# Adafruit_LED_Arcade_Button_1x4.net
KiCad netlist of a schematic drawn in EAGLE
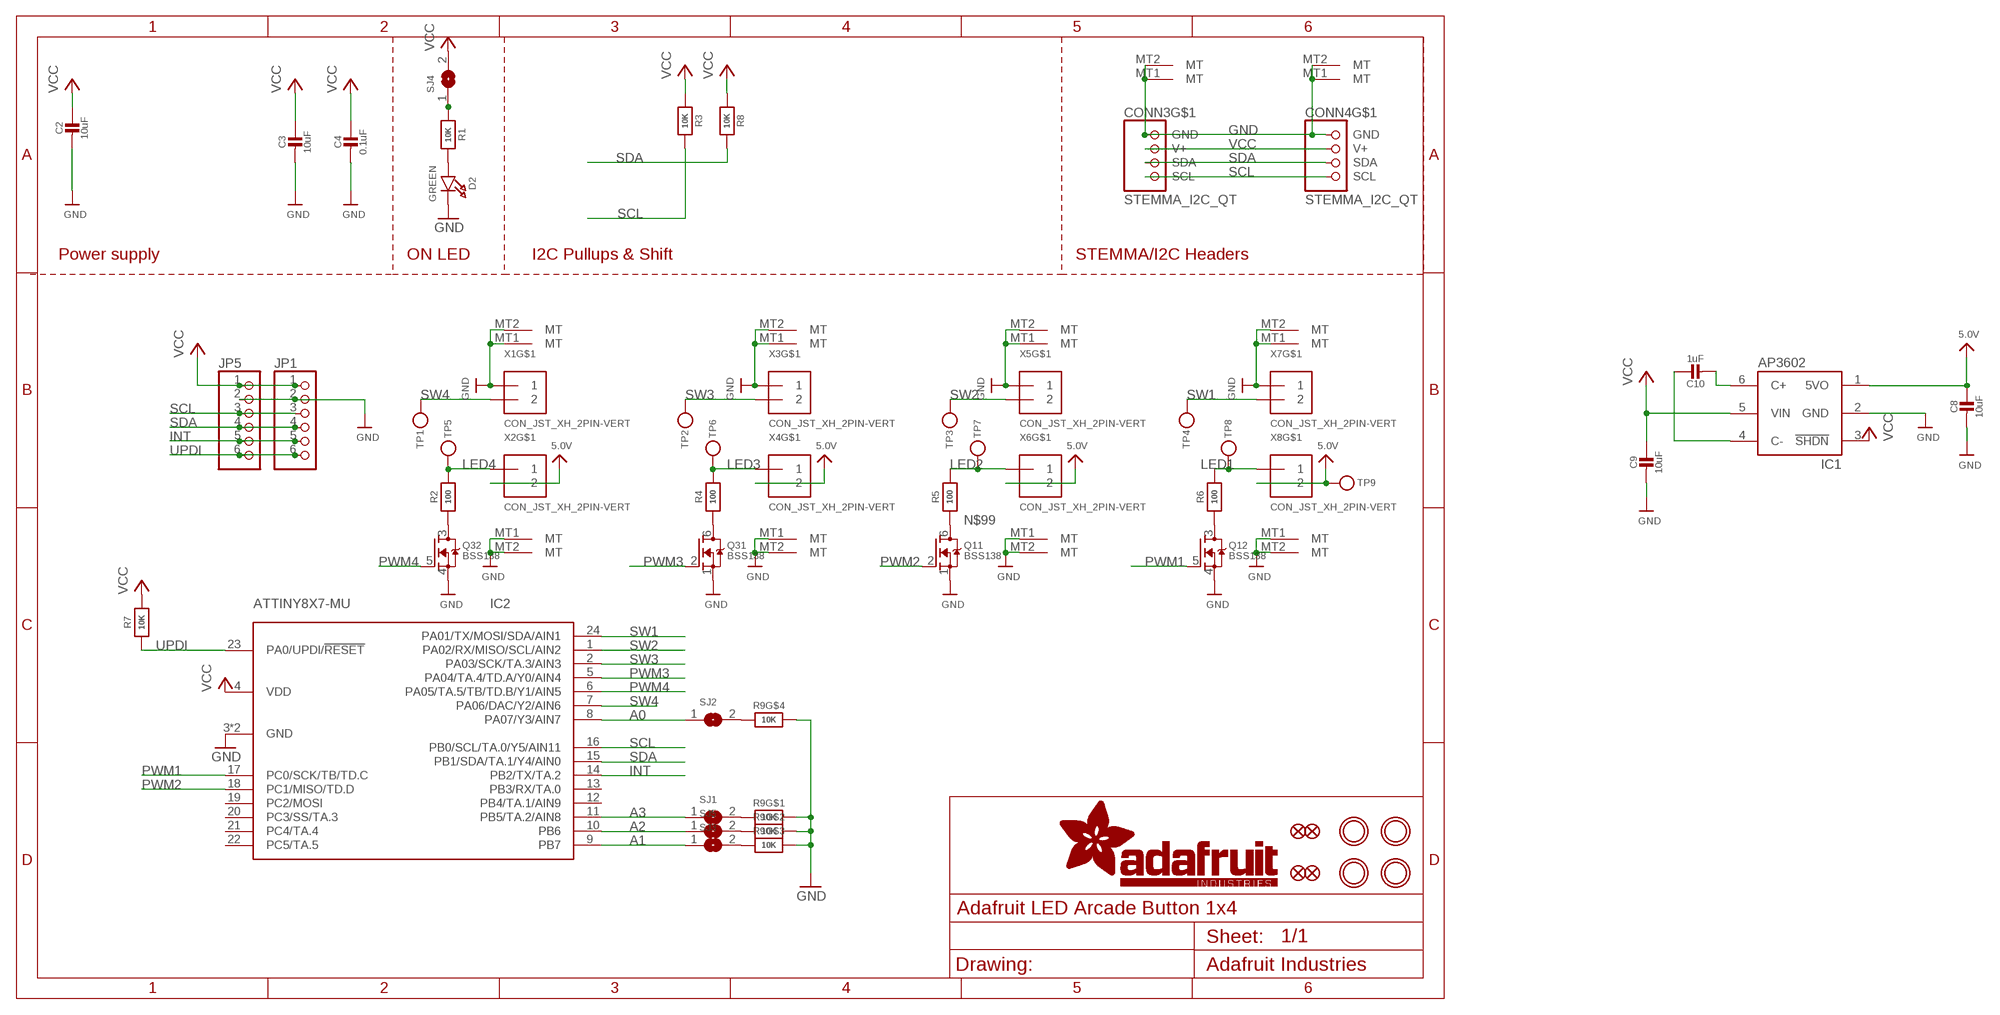
[diagram p0: schematic, sheet 1]

(export (version "E")
  (design (tool "Eeschema 10.0.6"))
  (components
    (comp (ref "C2")
      (value "10uF")
      (footprint "eagle-import:0805-NO")
      (libsource (lib "eagle-import") (part "CAP_CERAMIC0805-NOOUTLINE"))
    )
    (comp (ref "C3")
      (value "10uF")
      (footprint "eagle-import:0805-NO")
      (libsource (lib "eagle-import") (part "CAP_CERAMIC0805-NOOUTLINE"))
    )
    (comp (ref "C4")
      (value "0.1uF")
      (footprint "eagle-import:0603-NO")
      (libsource (lib "eagle-import") (part "CAP_CERAMIC0603_NO"))
    )
    (comp (ref "C8")
      (value "10uF")
      (footprint "eagle-import:0805-NO")
      (libsource (lib "eagle-import") (part "CAP_CERAMIC0805-NOOUTLINE"))
    )
    (comp (ref "C9")
      (value "10uF")
      (footprint "eagle-import:0805-NO")
      (libsource (lib "eagle-import") (part "CAP_CERAMIC0805-NOOUTLINE"))
    )
    (comp (ref "C10")
      (value "1uF")
      (footprint "eagle-import:0805-NO")
      (libsource (lib "eagle-import") (part "CAP_CERAMIC0805-NOOUTLINE"))
    )
    (comp (ref "CONN3")
      (value "STEMMA_I2C_QT")
      (footprint "eagle-import:JST_SH4")
      (libsource (lib "eagle-import") (part "STEMMA_I2C_QT"))
    )
    (comp (ref "CONN4")
      (value "STEMMA_I2C_QT")
      (footprint "eagle-import:JST_SH4")
      (libsource (lib "eagle-import") (part "STEMMA_I2C_QT"))
    )
    (comp (ref "D2")
      (value "GREEN")
      (footprint "eagle-import:CHIPLED_0603_NOOUTLINE")
      (libsource (lib "eagle-import") (part "LED0603_NOOUTLINE"))
    )
    (comp (ref "FID1")
      (value "FIDUCIAL_1MM")
      (footprint "eagle-import:FIDUCIAL_1MM")
      (libsource (lib "eagle-import") (part "FIDUCIAL_1MM"))
    )
    (comp (ref "FID2")
      (value "FIDUCIAL_1MM")
      (footprint "eagle-import:FIDUCIAL_1MM")
      (libsource (lib "eagle-import") (part "FIDUCIAL_1MM"))
    )
    (comp (ref "FID3")
      (value "FIDUCIAL_1MM")
      (footprint "eagle-import:FIDUCIAL_1MM")
      (libsource (lib "eagle-import") (part "FIDUCIAL_1MM"))
    )
    (comp (ref "FID4")
      (value "FIDUCIAL_1MM")
      (footprint "eagle-import:FIDUCIAL_1MM")
      (libsource (lib "eagle-import") (part "FIDUCIAL_1MM"))
    )
    (comp (ref "IC1")
      (value "AP3602")
      (footprint "eagle-import:SOT23-6")
      (libsource (lib "eagle-import") (part "AP3602"))
    )
    (comp (ref "IC2")
      (value "ATTINY8X7-MU")
      (footprint "eagle-import:QFN24_4MM")
      (libsource (lib "eagle-import") (part "ATTINY8X7-MU"))
    )
    (comp (ref "JP1")
      (value "HEADER-1X670MIL")
      (footprint "eagle-import:1X06_ROUND_70")
      (libsource (lib "eagle-import") (part "HEADER-1X670MIL"))
    )
    (comp (ref "JP5")
      (value "HEADER-1X670MIL")
      (footprint "eagle-import:1X06_ROUND_70")
      (libsource (lib "eagle-import") (part "HEADER-1X670MIL"))
    )
    (comp (ref "Q1")
      (value "BSS138")
      (footprint "eagle-import:SOT363")
      (libsource (lib "eagle-import") (part "MOSFET-N_DUAL"))
    )
    (comp (ref "Q3")
      (value "BSS138")
      (footprint "eagle-import:SOT363")
      (libsource (lib "eagle-import") (part "MOSFET-N_DUAL"))
    )
    (comp (ref "R1")
      (value "10K")
      (footprint "eagle-import:0603-NO")
      (libsource (lib "eagle-import") (part "RESISTOR_0603_NOOUT"))
    )
    (comp (ref "R2")
      (value "100")
      (footprint "eagle-import:0603-NO")
      (libsource (lib "eagle-import") (part "RESISTOR_0603_NOOUT"))
    )
    (comp (ref "R3")
      (value "10K")
      (footprint "eagle-import:0603-NO")
      (libsource (lib "eagle-import") (part "RESISTOR_0603_NOOUT"))
    )
    (comp (ref "R4")
      (value "100")
      (footprint "eagle-import:0603-NO")
      (libsource (lib "eagle-import") (part "RESISTOR_0603_NOOUT"))
    )
    (comp (ref "R5")
      (value "100")
      (footprint "eagle-import:0603-NO")
      (libsource (lib "eagle-import") (part "RESISTOR_0603_NOOUT"))
    )
    (comp (ref "R6")
      (value "100")
      (footprint "eagle-import:0603-NO")
      (libsource (lib "eagle-import") (part "RESISTOR_0603_NOOUT"))
    )
    (comp (ref "R7")
      (value "10K")
      (footprint "eagle-import:0603-NO")
      (libsource (lib "eagle-import") (part "RESISTOR_0603_NOOUT"))
    )
    (comp (ref "R8")
      (value "10K")
      (footprint "eagle-import:0603-NO")
      (libsource (lib "eagle-import") (part "RESISTOR_0603_NOOUT"))
    )
    (comp (ref "R9")
      (value "10K")
      (footprint "eagle-import:RESPACK_4X0603")
      (libsource (lib "eagle-import") (part "RESISTOR_4PACK"))
    )
    (comp (ref "SJ1")
      (value "SOLDERJUMPERCLOSED")
      (footprint "eagle-import:SOLDERJUMPER_CLOSEDWIRE")
      (libsource (lib "eagle-import") (part "SOLDERJUMPERCLOSED"))
    )
    (comp (ref "SJ2")
      (value "SOLDERJUMPERCLOSED")
      (footprint "eagle-import:SOLDERJUMPER_CLOSEDWIRE")
      (libsource (lib "eagle-import") (part "SOLDERJUMPERCLOSED"))
    )
    (comp (ref "SJ3")
      (value "SOLDERJUMPERCLOSED")
      (footprint "eagle-import:SOLDERJUMPER_CLOSEDWIRE")
      (libsource (lib "eagle-import") (part "SOLDERJUMPERCLOSED"))
    )
    (comp (ref "SJ4")
      (value "SOLDERJUMPERCLOSED")
      (footprint "eagle-import:SOLDERJUMPER_CLOSEDWIRE")
      (libsource (lib "eagle-import") (part "SOLDERJUMPERCLOSED"))
    )
    (comp (ref "SJ5")
      (value "SOLDERJUMPERCLOSED")
      (footprint "eagle-import:SOLDERJUMPER_CLOSEDWIRE")
      (libsource (lib "eagle-import") (part "SOLDERJUMPERCLOSED"))
    )
    (comp (ref "TP1")
      (value "TESTPOINTROUND1.5MM")
      (footprint "eagle-import:TESTPOINT_ROUND_1.5MM")
      (libsource (lib "eagle-import") (part "TESTPOINTROUND1.5MM"))
    )
    (comp (ref "TP2")
      (value "TESTPOINTROUND1.5MM")
      (footprint "eagle-import:TESTPOINT_ROUND_1.5MM")
      (libsource (lib "eagle-import") (part "TESTPOINTROUND1.5MM"))
    )
    (comp (ref "TP3")
      (value "TESTPOINTROUND1.5MM")
      (footprint "eagle-import:TESTPOINT_ROUND_1.5MM")
      (libsource (lib "eagle-import") (part "TESTPOINTROUND1.5MM"))
    )
    (comp (ref "TP4")
      (value "TESTPOINTROUND1.5MM")
      (footprint "eagle-import:TESTPOINT_ROUND_1.5MM")
      (libsource (lib "eagle-import") (part "TESTPOINTROUND1.5MM"))
    )
    (comp (ref "TP5")
      (value "TESTPOINTROUND1.5MM")
      (footprint "eagle-import:TESTPOINT_ROUND_1.5MM")
      (libsource (lib "eagle-import") (part "TESTPOINTROUND1.5MM"))
    )
    (comp (ref "TP6")
      (value "TESTPOINTROUND1.5MM")
      (footprint "eagle-import:TESTPOINT_ROUND_1.5MM")
      (libsource (lib "eagle-import") (part "TESTPOINTROUND1.5MM"))
    )
    (comp (ref "TP7")
      (value "TESTPOINTROUND1.5MM")
      (footprint "eagle-import:TESTPOINT_ROUND_1.5MM")
      (libsource (lib "eagle-import") (part "TESTPOINTROUND1.5MM"))
    )
    (comp (ref "TP8")
      (value "TESTPOINTROUND1.5MM")
      (footprint "eagle-import:TESTPOINT_ROUND_1.5MM")
      (libsource (lib "eagle-import") (part "TESTPOINTROUND1.5MM"))
    )
    (comp (ref "TP9")
      (value "TESTPOINTROUND1.5MM")
      (footprint "eagle-import:TESTPOINT_ROUND_1.5MM")
      (libsource (lib "eagle-import") (part "TESTPOINTROUND1.5MM"))
    )
    (comp (ref "U$3")
      (value "MOUNTINGHOLE2.5")
      (footprint "eagle-import:MOUNTINGHOLE_2.5_PLATED")
      (libsource (lib "eagle-import") (part "MOUNTINGHOLE2.5"))
    )
    (comp (ref "U$17")
      (value "MOUNTINGHOLE2.5")
      (footprint "eagle-import:MOUNTINGHOLE_2.5_PLATED")
      (libsource (lib "eagle-import") (part "MOUNTINGHOLE2.5"))
    )
    (comp (ref "U$19")
      (value "MOUNTINGHOLE2.5")
      (footprint "eagle-import:MOUNTINGHOLE_2.5_PLATED")
      (libsource (lib "eagle-import") (part "MOUNTINGHOLE2.5"))
    )
    (comp (ref "U$21")
      (value "MOUNTINGHOLE2.5")
      (footprint "eagle-import:MOUNTINGHOLE_2.5_PLATED")
      (libsource (lib "eagle-import") (part "MOUNTINGHOLE2.5"))
    )
    (comp (ref "X1")
      (value "CON_JST_XH_2PIN-VERT")
      (footprint "eagle-import:JST-XH-2-SV")
      (libsource (lib "eagle-import") (part "CON_JST_XH_2PIN-VERT"))
    )
    (comp (ref "X2")
      (value "CON_JST_XH_2PIN-VERT")
      (footprint "eagle-import:JST-XH-2-SV")
      (libsource (lib "eagle-import") (part "CON_JST_XH_2PIN-VERT"))
    )
    (comp (ref "X3")
      (value "CON_JST_XH_2PIN-VERT")
      (footprint "eagle-import:JST-XH-2-SV")
      (libsource (lib "eagle-import") (part "CON_JST_XH_2PIN-VERT"))
    )
    (comp (ref "X4")
      (value "CON_JST_XH_2PIN-VERT")
      (footprint "eagle-import:JST-XH-2-SV")
      (libsource (lib "eagle-import") (part "CON_JST_XH_2PIN-VERT"))
    )
    (comp (ref "X5")
      (value "CON_JST_XH_2PIN-VERT")
      (footprint "eagle-import:JST-XH-2-SV")
      (libsource (lib "eagle-import") (part "CON_JST_XH_2PIN-VERT"))
    )
    (comp (ref "X6")
      (value "CON_JST_XH_2PIN-VERT")
      (footprint "eagle-import:JST-XH-2-SV")
      (libsource (lib "eagle-import") (part "CON_JST_XH_2PIN-VERT"))
    )
    (comp (ref "X7")
      (value "CON_JST_XH_2PIN-VERT")
      (footprint "eagle-import:JST-XH-2-SV")
      (libsource (lib "eagle-import") (part "CON_JST_XH_2PIN-VERT"))
    )
    (comp (ref "X8")
      (value "CON_JST_XH_2PIN-VERT")
      (footprint "eagle-import:JST-XH-2-SV")
      (libsource (lib "eagle-import") (part "CON_JST_XH_2PIN-VERT"))
    )
  )
  (nets
    (net (code "1") (name "/A0") (class "Default")
      (node (ref "IC2") (pin "8") (pinfunction "PA07/Y3/AIN7_8") (pintype "bidirectional"))
      (node (ref "SJ2") (pin "1") (pinfunction "1_1") (pintype "passive"))
    )
    (net (code "2") (name "/A1") (class "Default")
      (node (ref "IC2") (pin "9") (pinfunction "PB7_9") (pintype "bidirectional"))
      (node (ref "SJ3") (pin "1") (pinfunction "1_1") (pintype "passive"))
    )
    (net (code "3") (name "/A2") (class "Default")
      (node (ref "IC2") (pin "10") (pinfunction "PB6_10") (pintype "bidirectional"))
      (node (ref "SJ5") (pin "1") (pinfunction "1_1") (pintype "passive"))
    )
    (net (code "4") (name "/A3") (class "Default")
      (node (ref "IC2") (pin "11") (pinfunction "PB5/TA.2/AIN8_11") (pintype "bidirectional"))
      (node (ref "SJ1") (pin "1") (pinfunction "1_1") (pintype "passive"))
    )
    (net (code "5") (name "/INT") (class "Default")
      (node (ref "IC2") (pin "14") (pinfunction "PB2/TX/TA.2_14") (pintype "bidirectional"))
      (node (ref "JP1") (pin "5") (pinfunction "5_5") (pintype "passive"))
      (node (ref "JP5") (pin "5") (pinfunction "5_5") (pintype "passive"))
    )
    (net (code "6") (name "/LED1") (class "Default")
      (node (ref "R6") (pin "2") (pinfunction "2_2") (pintype "passive"))
      (node (ref "TP8") (pin "P$1") (pinfunction "P$1_P$1") (pintype "bidirectional"))
      (node (ref "X8") (pin "1") (pinfunction "1_1") (pintype "passive"))
    )
    (net (code "7") (name "/LED2") (class "Default")
      (node (ref "R5") (pin "2") (pinfunction "2_2") (pintype "passive"))
      (node (ref "TP7") (pin "P$1") (pinfunction "P$1_P$1") (pintype "bidirectional"))
      (node (ref "X6") (pin "1") (pinfunction "1_1") (pintype "passive"))
    )
    (net (code "8") (name "/LED3") (class "Default")
      (node (ref "R4") (pin "2") (pinfunction "2_2") (pintype "passive"))
      (node (ref "TP6") (pin "P$1") (pinfunction "P$1_P$1") (pintype "bidirectional"))
      (node (ref "X4") (pin "1") (pinfunction "1_1") (pintype "passive"))
    )
    (net (code "9") (name "/LED4") (class "Default")
      (node (ref "R2") (pin "2") (pinfunction "2_2") (pintype "passive"))
      (node (ref "TP5") (pin "P$1") (pinfunction "P$1_P$1") (pintype "bidirectional"))
      (node (ref "X2") (pin "1") (pinfunction "1_1") (pintype "passive"))
    )
    (net (code "11") (name "/PWM1") (class "Default")
      (node (ref "IC2") (pin "17") (pinfunction "PC0/SCK/TB/TD.C_17") (pintype "bidirectional"))
      (node (ref "Q1") (pin "5") (pinfunction "G_5") (pintype "bidirectional"))
    )
    (net (code "12") (name "/PWM2") (class "Default")
      (node (ref "IC2") (pin "18") (pinfunction "PC1/MISO/TD.D_18") (pintype "bidirectional"))
      (node (ref "Q1") (pin "2") (pinfunction "G_2") (pintype "bidirectional"))
    )
    (net (code "13") (name "/PWM3") (class "Default")
      (node (ref "IC2") (pin "5") (pinfunction "PA04/TA.4/TD.A/Y0/AIN4_5") (pintype "bidirectional"))
      (node (ref "Q3") (pin "2") (pinfunction "G_2") (pintype "bidirectional"))
    )
    (net (code "14") (name "/PWM4") (class "Default")
      (node (ref "IC2") (pin "6") (pinfunction "PA05/TA.5/TB/TD.B/Y1/AIN5_6") (pintype "bidirectional"))
      (node (ref "Q3") (pin "5") (pinfunction "G_5") (pintype "bidirectional"))
    )
    (net (code "15") (name "/SCL") (class "Default")
      (node (ref "CONN3") (pin "4") (pinfunction "SCL_4") (pintype "passive"))
      (node (ref "CONN4") (pin "4") (pinfunction "SCL_4") (pintype "passive"))
      (node (ref "IC2") (pin "16") (pinfunction "PB0/SCL/TA.0/Y5/AIN11_16") (pintype "bidirectional"))
      (node (ref "JP1") (pin "3") (pinfunction "3_3") (pintype "passive"))
      (node (ref "JP5") (pin "3") (pinfunction "3_3") (pintype "passive"))
      (node (ref "R3") (pin "2") (pinfunction "2_2") (pintype "passive"))
    )
    (net (code "16") (name "/SDA") (class "Default")
      (node (ref "CONN3") (pin "3") (pinfunction "SDA_3") (pintype "passive"))
      (node (ref "CONN4") (pin "3") (pinfunction "SDA_3") (pintype "passive"))
      (node (ref "IC2") (pin "15") (pinfunction "PB1/SDA/TA.1/Y4/AIN0_15") (pintype "bidirectional"))
      (node (ref "JP1") (pin "4") (pinfunction "4_4") (pintype "passive"))
      (node (ref "JP5") (pin "4") (pinfunction "4_4") (pintype "passive"))
      (node (ref "R8") (pin "2") (pinfunction "2_2") (pintype "passive"))
    )
    (net (code "17") (name "/SW1") (class "Default")
      (node (ref "IC2") (pin "24") (pinfunction "PA01/TX/MOSI/SDA/AIN1_24") (pintype "bidirectional"))
      (node (ref "TP4") (pin "P$1") (pinfunction "P$1_P$1") (pintype "bidirectional"))
      (node (ref "X7") (pin "2") (pinfunction "2_2") (pintype "passive"))
    )
    (net (code "18") (name "/SW2") (class "Default")
      (node (ref "IC2") (pin "1") (pinfunction "PA02/RX/MISO/SCL/AIN2_1") (pintype "bidirectional"))
      (node (ref "TP3") (pin "P$1") (pinfunction "P$1_P$1") (pintype "bidirectional"))
      (node (ref "X5") (pin "2") (pinfunction "2_2") (pintype "passive"))
    )
    (net (code "19") (name "/SW3") (class "Default")
      (node (ref "IC2") (pin "2") (pinfunction "PA03/SCK/TA.3/AIN3_2") (pintype "bidirectional"))
      (node (ref "TP2") (pin "P$1") (pinfunction "P$1_P$1") (pintype "bidirectional"))
      (node (ref "X3") (pin "2") (pinfunction "2_2") (pintype "passive"))
    )
    (net (code "20") (name "/SW4") (class "Default")
      (node (ref "IC2") (pin "7") (pinfunction "PA06/DAC/Y2/AIN6_7") (pintype "bidirectional"))
      (node (ref "TP1") (pin "P$1") (pinfunction "P$1_P$1") (pintype "bidirectional"))
      (node (ref "X1") (pin "2") (pinfunction "2_2") (pintype "passive"))
    )
    (net (code "21") (name "/UPDI") (class "Default")
      (node (ref "IC2") (pin "23") (pinfunction "PA0/UPDI/~{RESET}_23") (pintype "bidirectional"))
      (node (ref "JP1") (pin "6") (pinfunction "6_6") (pintype "passive"))
      (node (ref "JP5") (pin "6") (pinfunction "6_6") (pintype "passive"))
      (node (ref "R7") (pin "1") (pinfunction "1_1") (pintype "passive"))
    )
    (net (code "22") (name "5.0V") (class "Default")
      (node (ref "C8") (pin "1") (pinfunction "1_1") (pintype "passive"))
      (node (ref "IC1") (pin "1") (pinfunction "5VO_1") (pintype "power_in"))
      (node (ref "TP9") (pin "P$1") (pinfunction "P$1_P$1") (pintype "bidirectional"))
      (node (ref "X2") (pin "2") (pinfunction "2_2") (pintype "passive"))
      (node (ref "X4") (pin "2") (pinfunction "2_2") (pintype "passive"))
      (node (ref "X6") (pin "2") (pinfunction "2_2") (pintype "passive"))
      (node (ref "X8") (pin "2") (pinfunction "2_2") (pintype "passive"))
    )
    (net (code "23") (name "GND") (class "Default")
      (node (ref "C2") (pin "2") (pinfunction "2_2") (pintype "passive"))
      (node (ref "C3") (pin "2") (pinfunction "2_2") (pintype "passive"))
      (node (ref "C4") (pin "2") (pinfunction "2_2") (pintype "passive"))
      (node (ref "C8") (pin "2") (pinfunction "2_2") (pintype "passive"))
      (node (ref "C9") (pin "2") (pinfunction "2_2") (pintype "passive"))
      (node (ref "CONN3") (pin "1") (pinfunction "GND_1") (pintype "passive"))
      (node (ref "CONN3") (pin "MT1") (pinfunction "MT_MT1") (pintype "bidirectional"))
      (node (ref "CONN3") (pin "MT2") (pinfunction "MT_MT2") (pintype "bidirectional"))
      (node (ref "CONN4") (pin "1") (pinfunction "GND_1") (pintype "passive"))
      (node (ref "CONN4") (pin "MT1") (pinfunction "MT_MT1") (pintype "bidirectional"))
      (node (ref "CONN4") (pin "MT2") (pinfunction "MT_MT2") (pintype "bidirectional"))
      (node (ref "D2") (pin "C") (pinfunction "C_C") (pintype "passive"))
      (node (ref "IC1") (pin "2") (pinfunction "GND_2") (pintype "power_in"))
      (node (ref "IC2") (pin "3") (pinfunction "GND_3") (pintype "power_in"))
      (node (ref "IC2") (pin "THERM") (pinfunction "GND_THERM") (pintype "power_in"))
      (node (ref "JP1") (pin "2") (pinfunction "2_2") (pintype "passive"))
      (node (ref "JP5") (pin "2") (pinfunction "2_2") (pintype "passive"))
      (node (ref "Q1") (pin "1") (pinfunction "S_1") (pintype "bidirectional"))
      (node (ref "Q1") (pin "4") (pinfunction "S_4") (pintype "bidirectional"))
      (node (ref "Q3") (pin "1") (pinfunction "S_1") (pintype "bidirectional"))
      (node (ref "Q3") (pin "4") (pinfunction "S_4") (pintype "bidirectional"))
      (node (ref "R9") (pin "5") (pinfunction "2_5") (pintype "passive"))
      (node (ref "R9") (pin "6") (pinfunction "2_6") (pintype "passive"))
      (node (ref "R9") (pin "7") (pinfunction "2_7") (pintype "passive"))
      (node (ref "R9") (pin "8") (pinfunction "2_8") (pintype "passive"))
      (node (ref "X1") (pin "1") (pinfunction "1_1") (pintype "passive"))
      (node (ref "X1") (pin "MT1") (pinfunction "MT_MT1") (pintype "bidirectional"))
      (node (ref "X1") (pin "MT2") (pinfunction "MT_MT2") (pintype "bidirectional"))
      (node (ref "X2") (pin "MT1") (pinfunction "MT_MT1") (pintype "bidirectional"))
      (node (ref "X2") (pin "MT2") (pinfunction "MT_MT2") (pintype "bidirectional"))
      (node (ref "X3") (pin "1") (pinfunction "1_1") (pintype "passive"))
      (node (ref "X3") (pin "MT1") (pinfunction "MT_MT1") (pintype "bidirectional"))
      (node (ref "X3") (pin "MT2") (pinfunction "MT_MT2") (pintype "bidirectional"))
      (node (ref "X4") (pin "MT1") (pinfunction "MT_MT1") (pintype "bidirectional"))
      (node (ref "X4") (pin "MT2") (pinfunction "MT_MT2") (pintype "bidirectional"))
      (node (ref "X5") (pin "1") (pinfunction "1_1") (pintype "passive"))
      (node (ref "X5") (pin "MT1") (pinfunction "MT_MT1") (pintype "bidirectional"))
      (node (ref "X5") (pin "MT2") (pinfunction "MT_MT2") (pintype "bidirectional"))
      (node (ref "X6") (pin "MT1") (pinfunction "MT_MT1") (pintype "bidirectional"))
      (node (ref "X6") (pin "MT2") (pinfunction "MT_MT2") (pintype "bidirectional"))
      (node (ref "X7") (pin "1") (pinfunction "1_1") (pintype "passive"))
      (node (ref "X7") (pin "MT1") (pinfunction "MT_MT1") (pintype "bidirectional"))
      (node (ref "X7") (pin "MT2") (pinfunction "MT_MT2") (pintype "bidirectional"))
      (node (ref "X8") (pin "MT1") (pinfunction "MT_MT1") (pintype "bidirectional"))
      (node (ref "X8") (pin "MT2") (pinfunction "MT_MT2") (pintype "bidirectional"))
    )
    (net (code "24") (name "Net-(D2-PadA)") (class "Default")
      (node (ref "D2") (pin "A") (pinfunction "A_A") (pintype "passive"))
      (node (ref "R1") (pin "2") (pinfunction "2_2") (pintype "passive"))
    )
    (net (code "25") (name "Net-(IC1-C+)") (class "Default")
      (node (ref "C10") (pin "2") (pinfunction "2_2") (pintype "passive"))
      (node (ref "IC1") (pin "6") (pinfunction "C+_6") (pintype "bidirectional"))
    )
    (net (code "26") (name "Net-(IC1-C-)") (class "Default")
      (node (ref "C10") (pin "1") (pinfunction "1_1") (pintype "passive"))
      (node (ref "IC1") (pin "4") (pinfunction "C-_4") (pintype "bidirectional"))
    )
    (net (code "27") (name "Net-(Q1A-D)") (class "Default")
      (node (ref "Q1") (pin "6") (pinfunction "D_6") (pintype "bidirectional"))
      (node (ref "R5") (pin "1") (pinfunction "1_1") (pintype "passive"))
    )
    (net (code "28") (name "Net-(Q1B-D)") (class "Default")
      (node (ref "Q1") (pin "3") (pinfunction "D_3") (pintype "bidirectional"))
      (node (ref "R6") (pin "1") (pinfunction "1_1") (pintype "passive"))
    )
    (net (code "29") (name "Net-(Q3A-D)") (class "Default")
      (node (ref "Q3") (pin "6") (pinfunction "D_6") (pintype "bidirectional"))
      (node (ref "R4") (pin "1") (pinfunction "1_1") (pintype "passive"))
    )
    (net (code "30") (name "Net-(Q3B-D)") (class "Default")
      (node (ref "Q3") (pin "3") (pinfunction "D_3") (pintype "bidirectional"))
      (node (ref "R2") (pin "1") (pinfunction "1_1") (pintype "passive"))
    )
    (net (code "31") (name "Net-(R1-Pad1)") (class "Default")
      (node (ref "R1") (pin "1") (pinfunction "1_1") (pintype "passive"))
      (node (ref "SJ4") (pin "1") (pinfunction "1_1") (pintype "passive"))
    )
    (net (code "32") (name "Net-(R9-Pad1)") (class "Default")
      (node (ref "R9") (pin "1") (pinfunction "1_1") (pintype "passive"))
      (node (ref "SJ1") (pin "2") (pinfunction "2_2") (pintype "passive"))
    )
    (net (code "33") (name "Net-(R9B-1)") (class "Default")
      (node (ref "R9") (pin "2") (pinfunction "1_2") (pintype "passive"))
      (node (ref "SJ5") (pin "2") (pinfunction "2_2") (pintype "passive"))
    )
    (net (code "34") (name "Net-(R9C-1)") (class "Default")
      (node (ref "R9") (pin "3") (pinfunction "1_3") (pintype "passive"))
      (node (ref "SJ3") (pin "2") (pinfunction "2_2") (pintype "passive"))
    )
    (net (code "35") (name "Net-(R9D-1)") (class "Default")
      (node (ref "R9") (pin "4") (pinfunction "1_4") (pintype "passive"))
      (node (ref "SJ2") (pin "2") (pinfunction "2_2") (pintype "passive"))
    )
    (net (code "36") (name "VCC") (class "Default")
      (node (ref "C2") (pin "1") (pinfunction "1_1") (pintype "passive"))
      (node (ref "C3") (pin "1") (pinfunction "1_1") (pintype "passive"))
      (node (ref "C4") (pin "1") (pinfunction "1_1") (pintype "passive"))
      (node (ref "C9") (pin "1") (pinfunction "1_1") (pintype "passive"))
      (node (ref "CONN3") (pin "2") (pinfunction "V+_2") (pintype "passive"))
      (node (ref "CONN4") (pin "2") (pinfunction "V+_2") (pintype "passive"))
      (node (ref "IC1") (pin "3") (pinfunction "~{SHDN}_3") (pintype "input"))
      (node (ref "IC1") (pin "5") (pinfunction "VIN_5") (pintype "power_in"))
      (node (ref "IC2") (pin "4") (pinfunction "VDD_4") (pintype "power_in"))
      (node (ref "JP1") (pin "1") (pinfunction "1_1") (pintype "passive"))
      (node (ref "JP5") (pin "1") (pinfunction "1_1") (pintype "passive"))
      (node (ref "R3") (pin "1") (pinfunction "1_1") (pintype "passive"))
      (node (ref "R7") (pin "2") (pinfunction "2_2") (pintype "passive"))
      (node (ref "R8") (pin "1") (pinfunction "1_1") (pintype "passive"))
      (node (ref "SJ4") (pin "2") (pinfunction "2_2") (pintype "passive"))
    )
    (net (code "37") (name "unconnected-(IC2-PB3{slash}RX{slash}TA.0-Pad13)") (class "Default")
      (node (ref "IC2") (pin "13") (pinfunction "PB3/RX/TA.0_13") (pintype "bidirectional"))
    )
    (net (code "38") (name "unconnected-(IC2-PB4{slash}TA.1{slash}AIN9-Pad12)") (class "Default")
      (node (ref "IC2") (pin "12") (pinfunction "PB4/TA.1/AIN9_12") (pintype "bidirectional"))
    )
    (net (code "39") (name "unconnected-(IC2-PC2{slash}MOSI-Pad19)") (class "Default")
      (node (ref "IC2") (pin "19") (pinfunction "PC2/MOSI_19") (pintype "bidirectional"))
    )
    (net (code "40") (name "unconnected-(IC2-PC3{slash}SS{slash}TA.3-Pad20)") (class "Default")
      (node (ref "IC2") (pin "20") (pinfunction "PC3/SS/TA.3_20") (pintype "bidirectional"))
    )
    (net (code "41") (name "unconnected-(IC2-PC4{slash}TA.4-Pad21)") (class "Default")
      (node (ref "IC2") (pin "21") (pinfunction "PC4/TA.4_21") (pintype "bidirectional"))
    )
    (net (code "42") (name "unconnected-(IC2-PC5{slash}TA.5-Pad22)") (class "Default")
      (node (ref "IC2") (pin "22") (pinfunction "PC5/TA.5_22") (pintype "bidirectional"))
    )
  )
)
